# Acquisition-System_V1_0_HMI.net
KiCad netlist of a schematic drawn in Altium Designer
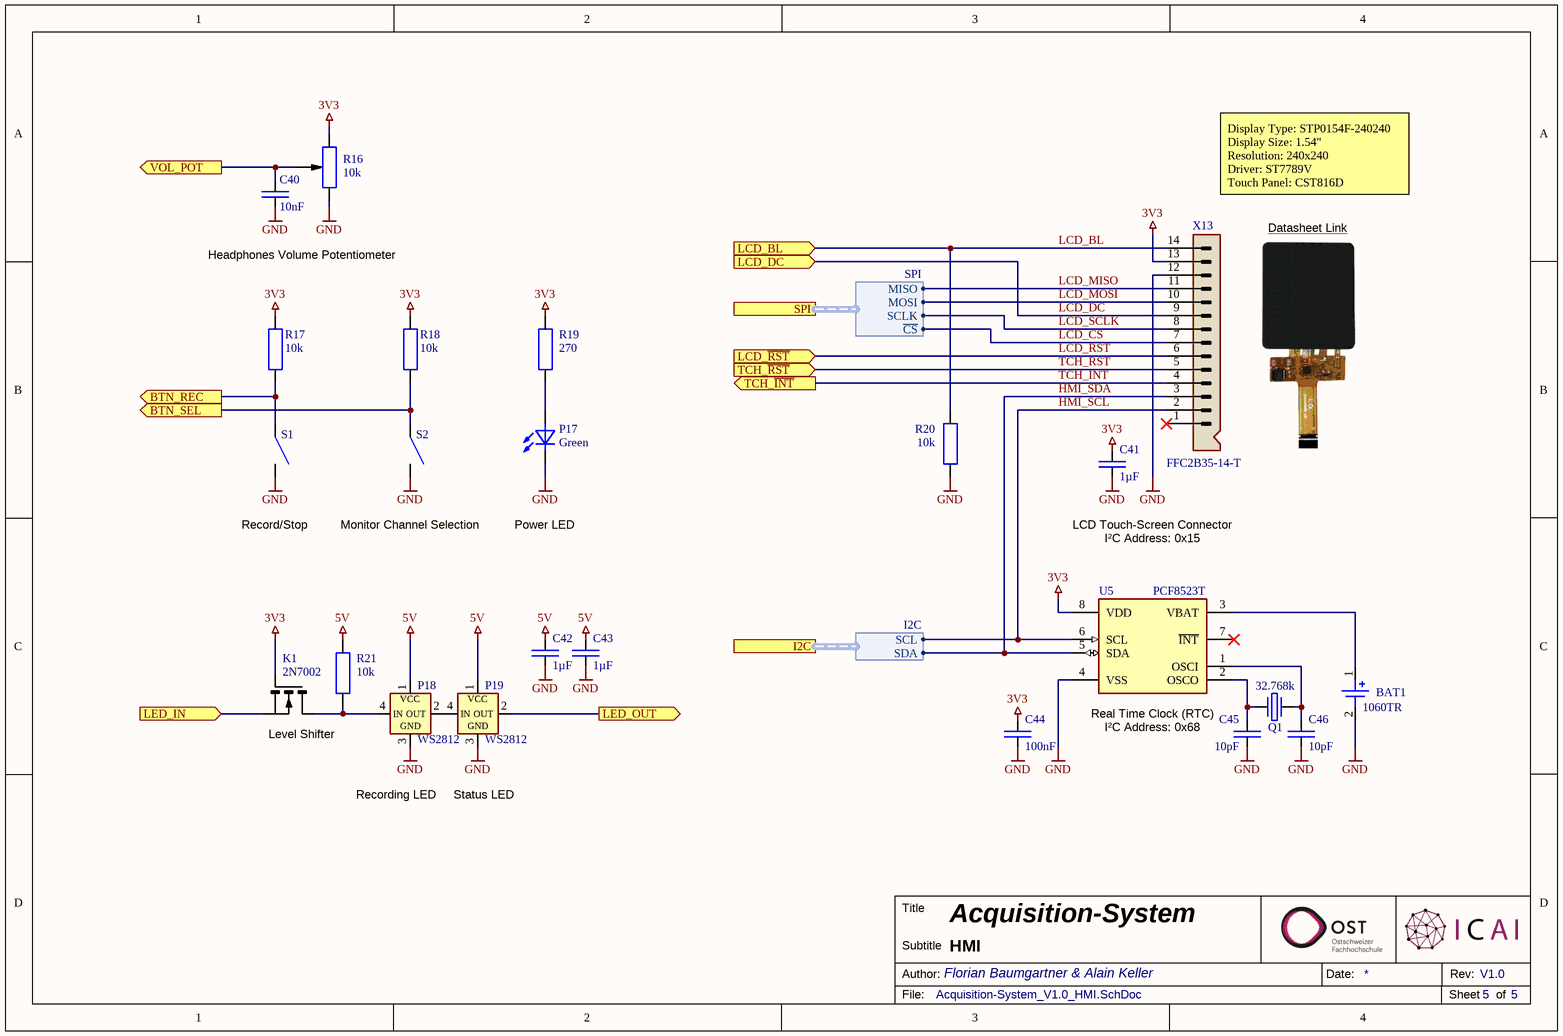
[diagram p0: Acquisition-System_V1.0_HMI.SchDoc]

(export (version "E")
  (design (tool "Eeschema 10.0.6"))
  (components
    (comp (ref "BAT1")
      (value "1060TR")
      (footprint "SMD Battery-Holder (1060TR)")
      (description "Battery Holder (CR2032)")
      (libsource (lib "Acquisition-System") (part "X-CR2032-Battery-Holder"))
    )
    (comp (ref "C40")
      (value "10nF")
      (footprint "SMD Keramikkondensator 0603")
      (description "CAP-MK")
      (libsource (lib "AudioAmp") (part "C-CAPACITOR"))
    )
    (comp (ref "C41")
      (value "1µF")
      (footprint "SMD Keramikkondensator 0603")
      (description "CAP-MK")
      (libsource (lib "AudioAmp") (part "C-CAPACITOR"))
    )
    (comp (ref "C42")
      (value "1µF")
      (footprint "SMD Keramikkondensator 0603")
      (description "CAP-MK")
      (libsource (lib "AudioAmp") (part "C-CAPACITOR"))
    )
    (comp (ref "C43")
      (value "1µF")
      (footprint "SMD Keramikkondensator 0603")
      (description "CAP-MK")
      (libsource (lib "AudioAmp") (part "C-CAPACITOR"))
    )
    (comp (ref "C44")
      (value "100nF")
      (footprint "SMD Keramikkondensator 0603")
      (description "SMD Ceramic Capacitor E6")
      (libsource (lib "Ceramic Capacitors-E6") (part "E6 - 100nF"))
    )
    (comp (ref "C45")
      (value "10pF")
      (footprint "SMD Keramikkondensator 0603")
      (description "CAP-MK")
      (libsource (lib "AudioAmp") (part "C-CAPACITOR"))
    )
    (comp (ref "C46")
      (value "10pF")
      (footprint "SMD Keramikkondensator 0603")
      (description "CAP-MK")
      (libsource (lib "AudioAmp") (part "C-CAPACITOR"))
    )
    (comp (ref "K1")
      (value "2N7002")
      (footprint "SMD MOSFET SOT-23")
      (description "MOSFET N-Channel")
      (libsource (lib "Nixie-Test") (part "K-FET{colon}NIGE"))
    )
    (comp (ref "P17")
      (value "Green")
      (footprint "SMD LED 0603")
      (description "General Purpose LED")
      (libsource (lib "Fleet-Monitor") (part "LED Green 0603"))
    )
    (comp (ref "P18")
      (value "WS2812")
      (footprint "SMD LED WS2812B-0807")
      (description "Smart RGB-LED")
      (libsource (lib "Acquisition-System") (part "P-WS2812B-0807"))
    )
    (comp (ref "P19")
      (value "WS2812")
      (footprint "SMD LED WS2812B-0807")
      (description "Smart RGB-LED")
      (libsource (lib "Acquisition-System") (part "P-WS2812B-0807"))
    )
    (comp (ref "Q1")
      (value "32.768k")
      (footprint "SMD Crystal 3.2x1.5x0.9")
      (libsource (lib "Acquisition-System") (part "Q-Crystal"))
    )
    (comp (ref "R16")
      (value "10k")
      (footprint "SMD Potentiometer (RK10J11R0A0H)")
      (description "RES-VAR")
      (libsource (lib "Acquisition-System") (part "R-RES{colon}VAR"))
    )
    (comp (ref "R17")
      (value "10k")
      (footprint "SMD Widerstand 0603")
      (description "RES (E=Heizwiderstand B=Messwandler)")
      (libsource (lib "TFS Integrated Library") (part "R-RESISTOR"))
    )
    (comp (ref "R18")
      (value "10k")
      (footprint "SMD Widerstand 0603")
      (description "RES (E=Heizwiderstand B=Messwandler)")
      (libsource (lib "TFS Integrated Library") (part "R-RESISTOR"))
    )
    (comp (ref "R19")
      (value "270")
      (footprint "SMD Widerstand 0603")
      (description "SMD-Widerstand 1/4W")
      (libsource (lib "Backplane_1") (part "R-RESISTOR"))
    )
    (comp (ref "R20")
      (value "10k")
      (footprint "SMD Widerstand 0603")
      (description "RES (E=Heizwiderstand B=Messwandler)")
      (libsource (lib "TFS Integrated Library") (part "R-RESISTOR"))
    )
    (comp (ref "R21")
      (value "10k")
      (footprint "SMD Widerstand 0603")
      (description "RES (E=Heizwiderstand B=Messwandler)")
      (libsource (lib "TFS Integrated Library") (part "R-RESISTOR"))
    )
    (comp (ref "S1")
      (value "SMD-Button")
      (footprint "SMD Button 6.5x6.0x2.5")
      (description "Button SPST")
      (libsource (lib "Switches") (part "Button 3mmx2.5mm"))
    )
    (comp (ref "S2")
      (value "SMD-Button")
      (footprint "SMD Button 6.5x6.0x2.5")
      (description "Button SPST")
      (libsource (lib "Switches") (part "Button 3mmx2.5mm"))
    )
    (comp (ref "U5")
      (value "PCF8523T")
      (footprint "SMD IC SOIC-8")
      (description "Real-Time Clock (RTC) and Calendar")
      (libsource (lib "Acquisition-System") (part "U-PCF8523T"))
    )
    (comp (ref "X13")
      (value "FFC2B35-14-T")
      (footprint "SMD Display 1.54\" (STP0154F-240240)")
      (description "FPC-Connector (14-Pin, Front Flip,  Bottom Contact)")
      (libsource (lib "Acquisition-System") (part "X-FPC-Connector (14-Pin)"))
    )
  )
  (nets
    (net (code "3") (name "/BTN_REC") (class "Default")
      (node (ref "R17") (pin "1") (pinfunction "1_1") (pintype "passive"))
      (node (ref "S1") (pin "1") (pinfunction "1_1") (pintype "passive"))
    )
    (net (code "4") (name "/BTN_SEL") (class "Default")
      (node (ref "R18") (pin "1") (pinfunction "1_1") (pintype "passive"))
      (node (ref "S2") (pin "1") (pinfunction "1_1") (pintype "passive"))
    )
    (net (code "5") (name "/HMI_SCL") (class "Default")
      (node (ref "U5") (pin "6") (pinfunction "SCL_6") (pintype "input"))
      (node (ref "X13") (pin "2") (pinfunction "2_2") (pintype "passive"))
    )
    (net (code "6") (name "/HMI_SDA") (class "Default")
      (node (ref "U5") (pin "5") (pinfunction "SDA_5") (pintype "bidirectional"))
      (node (ref "X13") (pin "3") (pinfunction "3_3") (pintype "passive"))
    )
    (net (code "7") (name "/LCD_BL") (class "Default")
      (node (ref "R20") (pin "2") (pinfunction "2_2") (pintype "passive"))
      (node (ref "X13") (pin "14") (pinfunction "14_14") (pintype "passive"))
    )
    (net (code "8") (name "/LCD_DC") (class "Default")
      (node (ref "X13") (pin "9") (pinfunction "9_9") (pintype "passive"))
    )
    (net (code "9") (name "/LCD_MISO") (class "Default")
      (node (ref "X13") (pin "11") (pinfunction "11_11") (pintype "passive"))
    )
    (net (code "10") (name "/LCD_MOSI") (class "Default")
      (node (ref "X13") (pin "10") (pinfunction "10_10") (pintype "passive"))
    )
    (net (code "11") (name "/LCD_SCLK") (class "Default")
      (node (ref "X13") (pin "8") (pinfunction "8_8") (pintype "passive"))
    )
    (net (code "12") (name "/LCD_~{CS}") (class "Default")
      (node (ref "X13") (pin "7") (pinfunction "7_7") (pintype "passive"))
    )
    (net (code "13") (name "/LCD_~{RST}") (class "Default")
      (node (ref "X13") (pin "6") (pinfunction "6_6") (pintype "passive"))
    )
    (net (code "14") (name "/LED_IN") (class "Default")
      (node (ref "K1") (pin "S") (pinfunction "S_S") (pintype "passive"))
    )
    (net (code "15") (name "/LED_OUT") (class "Default")
      (node (ref "P19") (pin "2") (pinfunction "OUT_2") (pintype "passive"))
    )
    (net (code "16") (name "/TCH_~{INT}") (class "Default")
      (node (ref "X13") (pin "4") (pinfunction "4_4") (pintype "passive"))
    )
    (net (code "17") (name "/TCH_~{RST}") (class "Default")
      (node (ref "X13") (pin "5") (pinfunction "5_5") (pintype "passive"))
    )
    (net (code "18") (name "/VOL_POT") (class "Default")
      (node (ref "C40") (pin "2") (pinfunction "2_2") (pintype "passive"))
      (node (ref "R16") (pin "M") (pinfunction "M_M") (pintype "passive"))
    )
    (net (code "21") (name "3V3") (class "Default")
      (node (ref "C41") (pin "2") (pinfunction "2_2") (pintype "passive"))
      (node (ref "C44") (pin "2") (pinfunction "2_2") (pintype "passive"))
      (node (ref "K1") (pin "G") (pinfunction "G_G") (pintype "passive"))
      (node (ref "R16") (pin "CCW") (pinfunction "CCW_CCW") (pintype "passive"))
      (node (ref "R17") (pin "2") (pinfunction "2_2") (pintype "passive"))
      (node (ref "R18") (pin "2") (pinfunction "2_2") (pintype "passive"))
      (node (ref "R19") (pin "1") (pinfunction "1_1") (pintype "passive"))
      (node (ref "U5") (pin "8") (pinfunction "VDD_8") (pintype "power_in"))
      (node (ref "X13") (pin "13") (pinfunction "13_13") (pintype "passive"))
    )
    (net (code "22") (name "5V") (class "Default")
      (node (ref "C42") (pin "2") (pinfunction "2_2") (pintype "passive"))
      (node (ref "C43") (pin "2") (pinfunction "2_2") (pintype "passive"))
      (node (ref "P18") (pin "1") (pinfunction "VCC_1") (pintype "power_in"))
      (node (ref "P19") (pin "1") (pinfunction "VCC_1") (pintype "power_in"))
      (node (ref "R21") (pin "2") (pinfunction "2_2") (pintype "passive"))
    )
    (net (code "23") (name "GND") (class "Default")
      (node (ref "BAT1") (pin "2") (pinfunction "N_2") (pintype "passive"))
      (node (ref "C40") (pin "1") (pinfunction "1_1") (pintype "passive"))
      (node (ref "C41") (pin "1") (pinfunction "1_1") (pintype "passive"))
      (node (ref "C42") (pin "1") (pinfunction "1_1") (pintype "passive"))
      (node (ref "C43") (pin "1") (pinfunction "1_1") (pintype "passive"))
      (node (ref "C44") (pin "1") (pinfunction "1_1") (pintype "passive"))
      (node (ref "C45") (pin "2") (pinfunction "2_2") (pintype "passive"))
      (node (ref "C46") (pin "2") (pinfunction "2_2") (pintype "passive"))
      (node (ref "P17") (pin "K") (pinfunction "K_K") (pintype "passive"))
      (node (ref "P18") (pin "3") (pinfunction "GND_3") (pintype "power_in"))
      (node (ref "P19") (pin "3") (pinfunction "GND_3") (pintype "power_in"))
      (node (ref "R16") (pin "CW") (pinfunction "CW_CW") (pintype "passive"))
      (node (ref "R20") (pin "1") (pinfunction "1_1") (pintype "passive"))
      (node (ref "S1") (pin "2") (pinfunction "2_2") (pintype "passive"))
      (node (ref "S2") (pin "2") (pinfunction "2_2") (pintype "passive"))
      (node (ref "U5") (pin "4") (pinfunction "VSS_4") (pintype "power_in"))
      (node (ref "X13") (pin "12") (pinfunction "12_12") (pintype "passive"))
    )
    (net (code "24") (name "Net-(BAT1-P)") (class "Default")
      (node (ref "BAT1") (pin "1") (pinfunction "P_1") (pintype "passive"))
      (node (ref "U5") (pin "3") (pinfunction "VBAT_3") (pintype "power_in"))
    )
    (net (code "25") (name "Net-(P17-PadA)") (class "Default")
      (node (ref "P17") (pin "A") (pinfunction "A_A") (pintype "passive"))
      (node (ref "R19") (pin "2") (pinfunction "2_2") (pintype "passive"))
    )
    (net (code "26") (name "Net-(P18-IN)") (class "Default")
      (node (ref "K1") (pin "D") (pinfunction "D_D") (pintype "passive"))
      (node (ref "P18") (pin "4") (pinfunction "IN_4") (pintype "passive"))
      (node (ref "R21") (pin "1") (pinfunction "1_1") (pintype "passive"))
    )
    (net (code "27") (name "Net-(P18-OUT)") (class "Default")
      (node (ref "P18") (pin "2") (pinfunction "OUT_2") (pintype "passive"))
      (node (ref "P19") (pin "4") (pinfunction "IN_4") (pintype "passive"))
    )
    (net (code "28") (name "Net-(U5-OSCI)") (class "Default")
      (node (ref "C46") (pin "1") (pinfunction "1_1") (pintype "passive"))
      (node (ref "Q1") (pin "2") (pinfunction "2_2") (pintype "passive"))
      (node (ref "U5") (pin "1") (pinfunction "OSCI_1") (pintype "passive"))
    )
    (net (code "29") (name "Net-(U5-OSCO)") (class "Default")
      (node (ref "C45") (pin "1") (pinfunction "1_1") (pintype "passive"))
      (node (ref "Q1") (pin "1") (pinfunction "1_1") (pintype "passive"))
      (node (ref "U5") (pin "2") (pinfunction "OSCO_2") (pintype "passive"))
    )
    (net (code "30") (name "unconnected-(U5-NC-Pad9)") (class "Default")
      (node (ref "U5") (pin "9") (pinfunction "NC_9") (pintype "passive"))
    )
    (net (code "31") (name "unconnected-(U5-NC-Pad10)") (class "Default")
      (node (ref "U5") (pin "10") (pinfunction "NC_10") (pintype "passive"))
    )
    (net (code "32") (name "unconnected-(U5-NC-Pad11)") (class "Default")
      (node (ref "U5") (pin "11") (pinfunction "NC_11") (pintype "passive"))
    )
    (net (code "33") (name "unconnected-(U5-~{INT}-Pad7)") (class "Default")
      (node (ref "U5") (pin "7") (pinfunction "~{INT}_7") (pintype "open_collector+no_connect"))
    )
    (net (code "34") (name "unconnected-(X13-Pad1)") (class "Default")
      (node (ref "X13") (pin "1") (pinfunction "1_1") (pintype "passive+no_connect"))
    )
  )
)
